# schematic-edited-source.net
KiCad netlist of a schematic drawn in EasyEDA
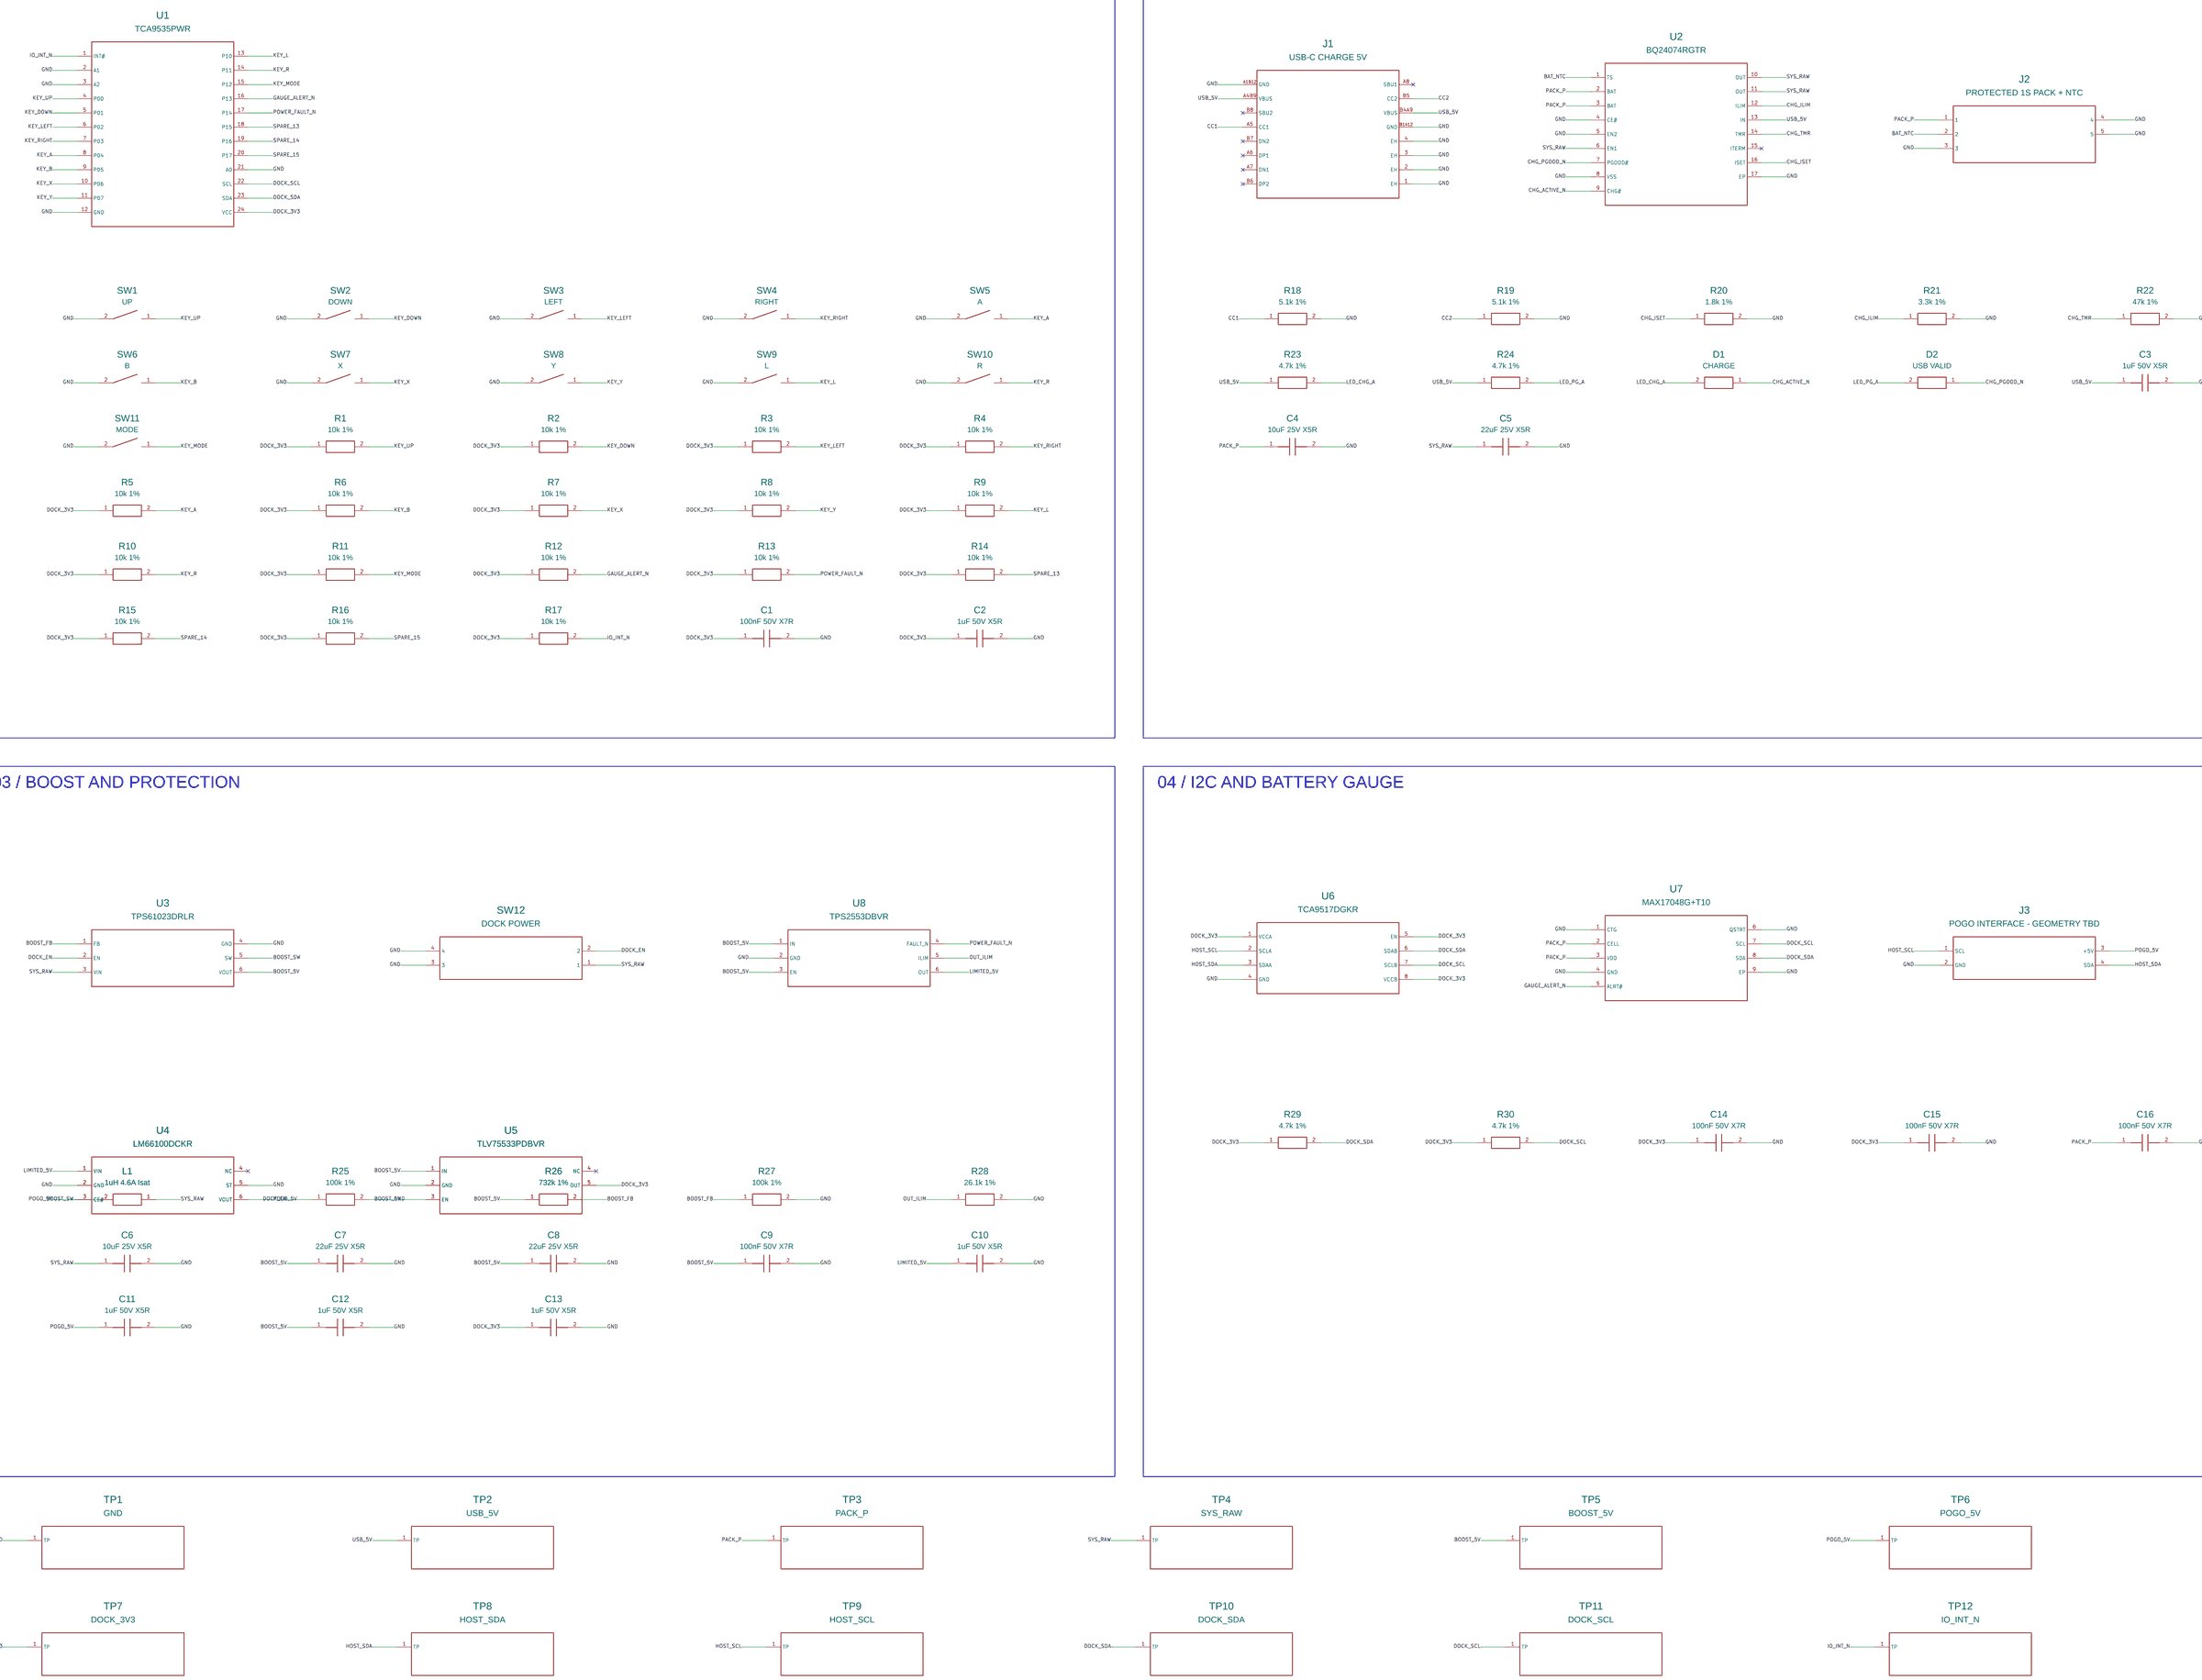
[diagram p0: schematic sheet]

(export (version "E")
  (design (tool "Eeschema 10.0.6"))
  (components
    (comp (ref "C1") (value "100nF 50V X7R") (libsource (lib "") (part "100nF 50V X7R")))
    (comp (ref "C2")
      (value "1uF 50V X5R")
      (fields
        (field (name "Manufacturer Part") "CL10A105KB8NNNC")
        (field (name "Manufacturer") "SAMSUNG(三星)")
      )
      (libsource (lib "") (part "1uF 50V X5R"))
    )
    (comp (ref "C3")
      (value "1uF 50V X5R")
      (fields
        (field (name "Manufacturer Part") "CL10A105KB8NNNC")
        (field (name "Manufacturer") "SAMSUNG(三星)")
      )
      (libsource (lib "") (part "1uF 50V X5R"))
    )
    (comp (ref "C4")
      (value "10uF 25V X5R")
      (fields
        (field (name "Manufacturer Part") "CL10A106MA8NRNC")
        (field (name "Manufacturer") "SAMSUNG(三星)")
      )
      (libsource (lib "") (part "10uF 25V X5R"))
    )
    (comp (ref "C5") (value "22uF 25V X5R") (libsource (lib "") (part "22uF 25V X5R")))
    (comp (ref "C6")
      (value "10uF 25V X5R")
      (fields
        (field (name "Manufacturer Part") "CL10A106MA8NRNC")
        (field (name "Manufacturer") "SAMSUNG(三星)")
      )
      (libsource (lib "") (part "10uF 25V X5R"))
    )
    (comp (ref "C7") (value "22uF 25V X5R") (libsource (lib "") (part "22uF 25V X5R")))
    (comp (ref "C8") (value "22uF 25V X5R") (libsource (lib "") (part "22uF 25V X5R")))
    (comp (ref "C9") (value "100nF 50V X7R") (libsource (lib "") (part "100nF 50V X7R")))
    (comp (ref "C10")
      (value "1uF 50V X5R")
      (fields
        (field (name "Manufacturer Part") "CL10A105KB8NNNC")
        (field (name "Manufacturer") "SAMSUNG(三星)")
      )
      (libsource (lib "") (part "1uF 50V X5R"))
    )
    (comp (ref "C11")
      (value "1uF 50V X5R")
      (fields
        (field (name "Manufacturer Part") "CL10A105KB8NNNC")
        (field (name "Manufacturer") "SAMSUNG(三星)")
      )
      (libsource (lib "") (part "1uF 50V X5R"))
    )
    (comp (ref "C12")
      (value "1uF 50V X5R")
      (fields
        (field (name "Manufacturer Part") "CL10A105KB8NNNC")
        (field (name "Manufacturer") "SAMSUNG(三星)")
      )
      (libsource (lib "") (part "1uF 50V X5R"))
    )
    (comp (ref "C13")
      (value "1uF 50V X5R")
      (fields
        (field (name "Manufacturer Part") "CL10A105KB8NNNC")
        (field (name "Manufacturer") "SAMSUNG(三星)")
      )
      (libsource (lib "") (part "1uF 50V X5R"))
    )
    (comp (ref "C14") (value "100nF 50V X7R") (libsource (lib "") (part "100nF 50V X7R")))
    (comp (ref "C15") (value "100nF 50V X7R") (libsource (lib "") (part "100nF 50V X7R")))
    (comp (ref "C16") (value "100nF 50V X7R") (libsource (lib "") (part "100nF 50V X7R")))
    (comp (ref "D1")
      (value "CHARGE")
      (fields (field (name "Manufacturer Part") "KT-0805黄灯") (field (name "Manufacturer") "KENTO"))
      (libsource (lib "") (part "CHARGE"))
    )
    (comp (ref "D2")
      (value "USB VALID")
      (fields (field (name "Manufacturer Part") "KT-0805黄灯") (field (name "Manufacturer") "KENTO"))
      (libsource (lib "") (part "USB VALID"))
    )
    (comp (ref "J1")
      (value "USB-C CHARGE 5V")
      (fields (field (name "Manufacturer Part") "TYPE-C-31-M-12") (field (name "Manufacturer") "韩国韩荣"))
      (libsource (lib "") (part "USB-C CHARGE 5V"))
    )
    (comp (ref "J2")
      (value "PROTECTED 1S PACK + NTC")
      (fields (field (name "Manufacturer Part") "B3B-PH-SM4-TB(LF)(SN)") (field (name "Manufacturer") "JST"))
      (libsource (lib "") (part "PROTECTED 1S PACK + NTC"))
    )
    (comp (ref "J3")
      (value "POGO INTERFACE - GEOMETRY TBD")
      (libsource (lib "") (part "POGO INTERFACE - GEOMETRY TBD"))
    )
    (comp (ref "L1")
      (value "1uH 4.6A Isat")
      (fields
        (field (name "Manufacturer Part") "FTC201610S1R0MBCA")
        (field (name "Manufacturer") "cjiang(长江微电)")
      )
      (libsource (lib "") (part "1uH 4.6A Isat"))
    )
    (comp (ref "R1")
      (value "10k 1%")
      (fields
        (field (name "Manufacturer Part") "0603WAF1002T5E")
        (field (name "Manufacturer") "UNI-ROYAL(厚声)")
      )
      (libsource (lib "") (part "10k 1%"))
    )
    (comp (ref "R2")
      (value "10k 1%")
      (fields
        (field (name "Manufacturer Part") "0603WAF1002T5E")
        (field (name "Manufacturer") "UNI-ROYAL(厚声)")
      )
      (libsource (lib "") (part "10k 1%"))
    )
    (comp (ref "R3")
      (value "10k 1%")
      (fields
        (field (name "Manufacturer Part") "0603WAF1002T5E")
        (field (name "Manufacturer") "UNI-ROYAL(厚声)")
      )
      (libsource (lib "") (part "10k 1%"))
    )
    (comp (ref "R4")
      (value "10k 1%")
      (fields
        (field (name "Manufacturer Part") "0603WAF1002T5E")
        (field (name "Manufacturer") "UNI-ROYAL(厚声)")
      )
      (libsource (lib "") (part "10k 1%"))
    )
    (comp (ref "R5")
      (value "10k 1%")
      (fields
        (field (name "Manufacturer Part") "0603WAF1002T5E")
        (field (name "Manufacturer") "UNI-ROYAL(厚声)")
      )
      (libsource (lib "") (part "10k 1%"))
    )
    (comp (ref "R6")
      (value "10k 1%")
      (fields
        (field (name "Manufacturer Part") "0603WAF1002T5E")
        (field (name "Manufacturer") "UNI-ROYAL(厚声)")
      )
      (libsource (lib "") (part "10k 1%"))
    )
    (comp (ref "R7")
      (value "10k 1%")
      (fields
        (field (name "Manufacturer Part") "0603WAF1002T5E")
        (field (name "Manufacturer") "UNI-ROYAL(厚声)")
      )
      (libsource (lib "") (part "10k 1%"))
    )
    (comp (ref "R8")
      (value "10k 1%")
      (fields
        (field (name "Manufacturer Part") "0603WAF1002T5E")
        (field (name "Manufacturer") "UNI-ROYAL(厚声)")
      )
      (libsource (lib "") (part "10k 1%"))
    )
    (comp (ref "R9")
      (value "10k 1%")
      (fields
        (field (name "Manufacturer Part") "0603WAF1002T5E")
        (field (name "Manufacturer") "UNI-ROYAL(厚声)")
      )
      (libsource (lib "") (part "10k 1%"))
    )
    (comp (ref "R10")
      (value "10k 1%")
      (fields
        (field (name "Manufacturer Part") "0603WAF1002T5E")
        (field (name "Manufacturer") "UNI-ROYAL(厚声)")
      )
      (libsource (lib "") (part "10k 1%"))
    )
    (comp (ref "R11")
      (value "10k 1%")
      (fields
        (field (name "Manufacturer Part") "0603WAF1002T5E")
        (field (name "Manufacturer") "UNI-ROYAL(厚声)")
      )
      (libsource (lib "") (part "10k 1%"))
    )
    (comp (ref "R12")
      (value "10k 1%")
      (fields
        (field (name "Manufacturer Part") "0603WAF1002T5E")
        (field (name "Manufacturer") "UNI-ROYAL(厚声)")
      )
      (libsource (lib "") (part "10k 1%"))
    )
    (comp (ref "R13")
      (value "10k 1%")
      (fields
        (field (name "Manufacturer Part") "0603WAF1002T5E")
        (field (name "Manufacturer") "UNI-ROYAL(厚声)")
      )
      (libsource (lib "") (part "10k 1%"))
    )
    (comp (ref "R14")
      (value "10k 1%")
      (fields
        (field (name "Manufacturer Part") "0603WAF1002T5E")
        (field (name "Manufacturer") "UNI-ROYAL(厚声)")
      )
      (libsource (lib "") (part "10k 1%"))
    )
    (comp (ref "R15")
      (value "10k 1%")
      (fields
        (field (name "Manufacturer Part") "0603WAF1002T5E")
        (field (name "Manufacturer") "UNI-ROYAL(厚声)")
      )
      (libsource (lib "") (part "10k 1%"))
    )
    (comp (ref "R16")
      (value "10k 1%")
      (fields
        (field (name "Manufacturer Part") "0603WAF1002T5E")
        (field (name "Manufacturer") "UNI-ROYAL(厚声)")
      )
      (libsource (lib "") (part "10k 1%"))
    )
    (comp (ref "R17")
      (value "10k 1%")
      (fields
        (field (name "Manufacturer Part") "0603WAF1002T5E")
        (field (name "Manufacturer") "UNI-ROYAL(厚声)")
      )
      (libsource (lib "") (part "10k 1%"))
    )
    (comp (ref "R18")
      (value "5.1k 1%")
      (fields
        (field (name "Manufacturer Part") "0603WAF5101T5E")
        (field (name "Manufacturer") "UNI-ROYAL(厚声)")
      )
      (libsource (lib "") (part "5.1k 1%"))
    )
    (comp (ref "R19")
      (value "5.1k 1%")
      (fields
        (field (name "Manufacturer Part") "0603WAF5101T5E")
        (field (name "Manufacturer") "UNI-ROYAL(厚声)")
      )
      (libsource (lib "") (part "5.1k 1%"))
    )
    (comp (ref "R20") (value "1.8k 1%") (libsource (lib "") (part "1.8k 1%")))
    (comp (ref "R21") (value "3.3k 1%") (libsource (lib "") (part "3.3k 1%")))
    (comp (ref "R22") (value "47k 1%") (libsource (lib "") (part "47k 1%")))
    (comp (ref "R23")
      (value "4.7k 1%")
      (fields
        (field (name "Manufacturer Part") "0603WAF4701T5E")
        (field (name "Manufacturer") "UNI-ROYAL(厚声)")
      )
      (libsource (lib "") (part "4.7k 1%"))
    )
    (comp (ref "R24")
      (value "4.7k 1%")
      (fields
        (field (name "Manufacturer Part") "0603WAF4701T5E")
        (field (name "Manufacturer") "UNI-ROYAL(厚声)")
      )
      (libsource (lib "") (part "4.7k 1%"))
    )
    (comp (ref "R25")
      (value "100k 1%")
      (fields
        (field (name "Manufacturer Part") "0603WAF1003T5E")
        (field (name "Manufacturer") "UNI-ROYAL(厚声)")
      )
      (libsource (lib "") (part "100k 1%"))
    )
    (comp (ref "R26") (value "732k 1%") (libsource (lib "") (part "732k 1%")))
    (comp (ref "R27")
      (value "100k 1%")
      (fields
        (field (name "Manufacturer Part") "0603WAF1003T5E")
        (field (name "Manufacturer") "UNI-ROYAL(厚声)")
      )
      (libsource (lib "") (part "100k 1%"))
    )
    (comp (ref "R28") (value "26.1k 1%") (libsource (lib "") (part "26.1k 1%")))
    (comp (ref "R29")
      (value "4.7k 1%")
      (fields
        (field (name "Manufacturer Part") "0603WAF4701T5E")
        (field (name "Manufacturer") "UNI-ROYAL(厚声)")
      )
      (libsource (lib "") (part "4.7k 1%"))
    )
    (comp (ref "R30")
      (value "4.7k 1%")
      (fields
        (field (name "Manufacturer Part") "0603WAF4701T5E")
        (field (name "Manufacturer") "UNI-ROYAL(厚声)")
      )
      (libsource (lib "") (part "4.7k 1%"))
    )
    (comp (ref "SW1")
      (value "UP")
      (fields (field (name "Manufacturer Part") "TS-1088-AR02016") (field (name "Manufacturer") "XUNPU(讯普)"))
      (libsource (lib "") (part "UP"))
    )
    (comp (ref "SW2")
      (value "DOWN")
      (fields (field (name "Manufacturer Part") "TS-1088-AR02016") (field (name "Manufacturer") "XUNPU(讯普)"))
      (libsource (lib "") (part "DOWN"))
    )
    (comp (ref "SW3")
      (value "LEFT")
      (fields (field (name "Manufacturer Part") "TS-1088-AR02016") (field (name "Manufacturer") "XUNPU(讯普)"))
      (libsource (lib "") (part "LEFT"))
    )
    (comp (ref "SW4")
      (value "RIGHT")
      (fields (field (name "Manufacturer Part") "TS-1088-AR02016") (field (name "Manufacturer") "XUNPU(讯普)"))
      (libsource (lib "") (part "RIGHT"))
    )
    (comp (ref "SW5")
      (value "A")
      (fields (field (name "Manufacturer Part") "TS-1088-AR02016") (field (name "Manufacturer") "XUNPU(讯普)"))
      (libsource (lib "") (part "A"))
    )
    (comp (ref "SW6")
      (value "B")
      (fields (field (name "Manufacturer Part") "TS-1088-AR02016") (field (name "Manufacturer") "XUNPU(讯普)"))
      (libsource (lib "") (part "B"))
    )
    (comp (ref "SW7")
      (value "X")
      (fields (field (name "Manufacturer Part") "TS-1088-AR02016") (field (name "Manufacturer") "XUNPU(讯普)"))
      (libsource (lib "") (part "X"))
    )
    (comp (ref "SW8")
      (value "Y")
      (fields (field (name "Manufacturer Part") "TS-1088-AR02016") (field (name "Manufacturer") "XUNPU(讯普)"))
      (libsource (lib "") (part "Y"))
    )
    (comp (ref "SW9")
      (value "L")
      (fields (field (name "Manufacturer Part") "TS-1088-AR02016") (field (name "Manufacturer") "XUNPU(讯普)"))
      (libsource (lib "") (part "L"))
    )
    (comp (ref "SW10")
      (value "R")
      (fields (field (name "Manufacturer Part") "TS-1088-AR02016") (field (name "Manufacturer") "XUNPU(讯普)"))
      (libsource (lib "") (part "R"))
    )
    (comp (ref "SW11")
      (value "MODE")
      (fields (field (name "Manufacturer Part") "TS-1088-AR02016") (field (name "Manufacturer") "XUNPU(讯普)"))
      (libsource (lib "") (part "MODE"))
    )
    (comp (ref "SW12")
      (value "DOCK POWER")
      (fields (field (name "Manufacturer Part") "MSK12C02") (field (name "Manufacturer") "SHOU HAN(首韩)"))
      (libsource (lib "") (part "DOCK POWER"))
    )
    (comp (ref "TP1") (value "GND") (libsource (lib "") (part "GND")))
    (comp (ref "TP2") (value "USB_5V") (libsource (lib "") (part "USB_5V")))
    (comp (ref "TP3") (value "PACK_P") (libsource (lib "") (part "PACK_P")))
    (comp (ref "TP4") (value "SYS_RAW") (libsource (lib "") (part "SYS_RAW")))
    (comp (ref "TP5") (value "BOOST_5V") (libsource (lib "") (part "BOOST_5V")))
    (comp (ref "TP6") (value "POGO_5V") (libsource (lib "") (part "POGO_5V")))
    (comp (ref "TP7") (value "DOCK_3V3") (libsource (lib "") (part "DOCK_3V3")))
    (comp (ref "TP8") (value "HOST_SDA") (libsource (lib "") (part "HOST_SDA")))
    (comp (ref "TP9") (value "HOST_SCL") (libsource (lib "") (part "HOST_SCL")))
    (comp (ref "TP10") (value "DOCK_SDA") (libsource (lib "") (part "DOCK_SDA")))
    (comp (ref "TP11") (value "DOCK_SCL") (libsource (lib "") (part "DOCK_SCL")))
    (comp (ref "TP12") (value "IO_INT_N") (libsource (lib "") (part "IO_INT_N")))
    (comp (ref "U1")
      (value "TCA9535PWR")
      (fields (field (name "Manufacturer") "TI(德州仪器)"))
      (libsource (lib "") (part "TCA9535PWR"))
    )
    (comp (ref "U2")
      (value "BQ24074RGTR")
      (fields (field (name "Manufacturer") "TI(德州仪器)"))
      (libsource (lib "") (part "BQ24074RGTR"))
    )
    (comp (ref "U3")
      (value "TPS61023DRLR")
      (fields (field (name "Manufacturer") "TI(德州仪器)"))
      (libsource (lib "") (part "TPS61023DRLR"))
    )
    (comp (ref "U4")
      (value "LM66100DCKR")
      (fields (field (name "Manufacturer") "TI(德州仪器)"))
      (libsource (lib "") (part "LM66100DCKR"))
    )
    (comp (ref "U5")
      (value "TLV75533PDBVR")
      (fields (field (name "Manufacturer") "TI(德州仪器)"))
      (libsource (lib "") (part "TLV75533PDBVR"))
    )
    (comp (ref "U6")
      (value "TCA9517DGKR")
      (fields (field (name "Manufacturer") "TI(德州仪器)"))
      (libsource (lib "") (part "TCA9517DGKR"))
    )
    (comp (ref "U7")
      (value "MAX17048G+T10")
      (fields (field (name "Manufacturer") "ADI(亚德诺)/MAXIM(美信)"))
      (libsource (lib "") (part "MAX17048G+T10"))
    )
    (comp (ref "U8") (value "TPS2553DBVR") (libsource (lib "") (part "TPS2553DBVR")))
  )
  (nets
    (net (code "1") (name "/BAT_NTC") (class "Default")
      (node (ref "J2") (pin "2") (pinfunction "2_2") (pintype "unspecified"))
      (node (ref "U2") (pin "1") (pinfunction "TS_1") (pintype "unspecified"))
    )
    (net (code "2") (name "/BOOST_5V") (class "Default")
      (node (ref "C12") (pin "1") (pintype "unspecified"))
      (node (ref "C7") (pin "1") (pintype "unspecified"))
      (node (ref "C8") (pin "1") (pintype "unspecified"))
      (node (ref "C9") (pin "1") (pintype "unspecified"))
      (node (ref "R26") (pin "1") (pintype "unspecified"))
      (node (ref "TP5") (pin "1") (pinfunction "TP_1") (pintype "unspecified"))
      (node (ref "U3") (pin "6") (pinfunction "VOUT_6") (pintype "unspecified"))
      (node (ref "U5") (pin "1") (pinfunction "IN_1") (pintype "unspecified"))
      (node (ref "U5") (pin "3") (pinfunction "EN_3") (pintype "unspecified"))
      (node (ref "U8") (pin "1") (pinfunction "IN_1") (pintype "unspecified"))
      (node (ref "U8") (pin "3") (pinfunction "EN_3") (pintype "unspecified"))
    )
    (net (code "3") (name "/BOOST_FB") (class "Default")
      (node (ref "R26") (pin "2") (pintype "unspecified"))
      (node (ref "R27") (pin "1") (pintype "unspecified"))
      (node (ref "U3") (pin "1") (pinfunction "FB_1") (pintype "unspecified"))
    )
    (net (code "4") (name "/BOOST_SW") (class "Default")
      (node (ref "C11") (pin "1") (pintype "unspecified"))
      (node (ref "J3") (pin "3") (pinfunction "+5V_3") (pintype "unspecified"))
      (node (ref "L1") (pin "2") (pintype "unspecified"))
      (node (ref "TP6") (pin "1") (pinfunction "TP_1") (pintype "unspecified"))
      (node (ref "U3") (pin "5") (pinfunction "SW_5") (pintype "unspecified"))
      (node (ref "U4") (pin "3") (pinfunction "CE#_3") (pintype "unspecified"))
      (node (ref "U4") (pin "6") (pinfunction "VOUT_6") (pintype "unspecified"))
    )
    (net (code "5") (name "/CC1") (class "Default")
      (node (ref "J1") (pin "A5") (pinfunction "CC1_A5") (pintype "unspecified"))
      (node (ref "R18") (pin "1") (pintype "unspecified"))
    )
    (net (code "6") (name "/CC2") (class "Default")
      (node (ref "J1") (pin "B5") (pinfunction "CC2_B5") (pintype "unspecified"))
      (node (ref "R19") (pin "1") (pintype "unspecified"))
    )
    (net (code "7") (name "/CHG_ACTIVE_N") (class "Default")
      (node (ref "D1") (pin "1") (pintype "unspecified"))
      (node (ref "U2") (pin "9") (pinfunction "CHG#_9") (pintype "unspecified"))
    )
    (net (code "8") (name "/CHG_ILIM") (class "Default")
      (node (ref "R21") (pin "1") (pintype "unspecified"))
      (node (ref "U2") (pin "12") (pinfunction "ILIM_12") (pintype "unspecified"))
    )
    (net (code "9") (name "/CHG_ISET") (class "Default")
      (node (ref "R20") (pin "1") (pintype "unspecified"))
      (node (ref "U2") (pin "16") (pinfunction "ISET_16") (pintype "unspecified"))
    )
    (net (code "10") (name "/CHG_PGOOD_N") (class "Default")
      (node (ref "D2") (pin "1") (pintype "unspecified"))
      (node (ref "U2") (pin "7") (pinfunction "PGOOD#_7") (pintype "unspecified"))
    )
    (net (code "11") (name "/CHG_TMR") (class "Default")
      (node (ref "R22") (pin "1") (pintype "unspecified"))
      (node (ref "U2") (pin "14") (pinfunction "TMR_14") (pintype "unspecified"))
    )
    (net (code "12") (name "/DOCK_3V3") (class "Default")
      (node (ref "C1") (pin "1") (pintype "unspecified"))
      (node (ref "C13") (pin "1") (pintype "unspecified"))
      (node (ref "C14") (pin "1") (pintype "unspecified"))
      (node (ref "C15") (pin "1") (pintype "unspecified"))
      (node (ref "C2") (pin "1") (pintype "unspecified"))
      (node (ref "R1") (pin "1") (pintype "unspecified"))
      (node (ref "R10") (pin "1") (pintype "unspecified"))
      (node (ref "R11") (pin "1") (pintype "unspecified"))
      (node (ref "R12") (pin "1") (pintype "unspecified"))
      (node (ref "R13") (pin "1") (pintype "unspecified"))
      (node (ref "R14") (pin "1") (pintype "unspecified"))
      (node (ref "R15") (pin "1") (pintype "unspecified"))
      (node (ref "R16") (pin "1") (pintype "unspecified"))
      (node (ref "R17") (pin "1") (pintype "unspecified"))
      (node (ref "R2") (pin "1") (pintype "unspecified"))
      (node (ref "R29") (pin "1") (pintype "unspecified"))
      (node (ref "R3") (pin "1") (pintype "unspecified"))
      (node (ref "R30") (pin "1") (pintype "unspecified"))
      (node (ref "R4") (pin "1") (pintype "unspecified"))
      (node (ref "R5") (pin "1") (pintype "unspecified"))
      (node (ref "R6") (pin "1") (pintype "unspecified"))
      (node (ref "R7") (pin "1") (pintype "unspecified"))
      (node (ref "R8") (pin "1") (pintype "unspecified"))
      (node (ref "R9") (pin "1") (pintype "unspecified"))
      (node (ref "TP7") (pin "1") (pinfunction "TP_1") (pintype "unspecified"))
      (node (ref "U1") (pin "24") (pinfunction "VCC_24") (pintype "unspecified"))
      (node (ref "U5") (pin "5") (pinfunction "OUT_5") (pintype "unspecified"))
      (node (ref "U6") (pin "1") (pinfunction "VCCA_1") (pintype "unspecified"))
      (node (ref "U6") (pin "5") (pinfunction "EN_5") (pintype "unspecified"))
      (node (ref "U6") (pin "8") (pinfunction "VCCB_8") (pintype "unspecified"))
    )
    (net (code "13") (name "/DOCK_EN") (class "Default")
      (node (ref "R25") (pin "1") (pintype "unspecified"))
      (node (ref "SW12") (pin "2") (pinfunction "2_2") (pintype "unspecified"))
      (node (ref "U3") (pin "2") (pinfunction "EN_2") (pintype "unspecified"))
    )
    (net (code "14") (name "/DOCK_SCL") (class "Default")
      (node (ref "R30") (pin "2") (pintype "unspecified"))
      (node (ref "TP11") (pin "1") (pinfunction "TP_1") (pintype "unspecified"))
      (node (ref "U1") (pin "22") (pinfunction "SCL_22") (pintype "unspecified"))
      (node (ref "U6") (pin "7") (pinfunction "SCLB_7") (pintype "unspecified"))
      (node (ref "U7") (pin "7") (pinfunction "SCL_7") (pintype "unspecified"))
    )
    (net (code "15") (name "/DOCK_SDA") (class "Default")
      (node (ref "R29") (pin "2") (pintype "unspecified"))
      (node (ref "TP10") (pin "1") (pinfunction "TP_1") (pintype "unspecified"))
      (node (ref "U1") (pin "23") (pinfunction "SDA_23") (pintype "unspecified"))
      (node (ref "U6") (pin "6") (pinfunction "SDAB_6") (pintype "unspecified"))
      (node (ref "U7") (pin "8") (pinfunction "SDA_8") (pintype "unspecified"))
    )
    (net (code "16") (name "/GAUGE_ALERT_N") (class "Default")
      (node (ref "R12") (pin "2") (pintype "unspecified"))
      (node (ref "U1") (pin "16") (pinfunction "P13_16") (pintype "unspecified"))
      (node (ref "U7") (pin "5") (pinfunction "ALRT#_5") (pintype "unspecified"))
    )
    (net (code "17") (name "/GND") (class "Default")
      (node (ref "C1") (pin "2") (pintype "unspecified"))
      (node (ref "C10") (pin "2") (pintype "unspecified"))
      (node (ref "C11") (pin "2") (pintype "unspecified"))
      (node (ref "C12") (pin "2") (pintype "unspecified"))
      (node (ref "C13") (pin "2") (pintype "unspecified"))
      (node (ref "C14") (pin "2") (pintype "unspecified"))
      (node (ref "C15") (pin "2") (pintype "unspecified"))
      (node (ref "C16") (pin "2") (pintype "unspecified"))
      (node (ref "C2") (pin "2") (pintype "unspecified"))
      (node (ref "C3") (pin "2") (pintype "unspecified"))
      (node (ref "C4") (pin "2") (pintype "unspecified"))
      (node (ref "C5") (pin "2") (pintype "unspecified"))
      (node (ref "C6") (pin "2") (pintype "unspecified"))
      (node (ref "C7") (pin "2") (pintype "unspecified"))
      (node (ref "C8") (pin "2") (pintype "unspecified"))
      (node (ref "C9") (pin "2") (pintype "unspecified"))
      (node (ref "J1") (pin "1") (pinfunction "EH_1") (pintype "unspecified"))
      (node (ref "J1") (pin "2") (pinfunction "EH_2") (pintype "unspecified"))
      (node (ref "J1") (pin "3") (pinfunction "EH_3") (pintype "unspecified"))
      (node (ref "J1") (pin "4") (pinfunction "EH_4") (pintype "unspecified"))
      (node (ref "J1") (pin "A1B12") (pinfunction "GND_A1B12") (pintype "unspecified"))
      (node (ref "J1") (pin "B1A12") (pinfunction "GND_B1A12") (pintype "unspecified"))
      (node (ref "J2") (pin "3") (pinfunction "3_3") (pintype "unspecified"))
      (node (ref "J2") (pin "4") (pinfunction "4_4") (pintype "unspecified"))
      (node (ref "J2") (pin "5") (pinfunction "5_5") (pintype "unspecified"))
      (node (ref "J3") (pin "2") (pinfunction "GND_2") (pintype "unspecified"))
      (node (ref "R18") (pin "2") (pintype "unspecified"))
      (node (ref "R19") (pin "2") (pintype "unspecified"))
      (node (ref "R20") (pin "2") (pintype "unspecified"))
      (node (ref "R21") (pin "2") (pintype "unspecified"))
      (node (ref "R22") (pin "2") (pintype "unspecified"))
      (node (ref "R25") (pin "2") (pintype "unspecified"))
      (node (ref "R27") (pin "2") (pintype "unspecified"))
      (node (ref "R28") (pin "2") (pintype "unspecified"))
      (node (ref "SW1") (pin "2") (pintype "unspecified"))
      (node (ref "SW10") (pin "2") (pintype "unspecified"))
      (node (ref "SW11") (pin "2") (pintype "unspecified"))
      (node (ref "SW12") (pin "3") (pinfunction "3_3") (pintype "unspecified"))
      (node (ref "SW12") (pin "4") (pinfunction "4_4") (pintype "unspecified"))
      (node (ref "SW2") (pin "2") (pintype "unspecified"))
      (node (ref "SW3") (pin "2") (pintype "unspecified"))
      (node (ref "SW4") (pin "2") (pintype "unspecified"))
      (node (ref "SW5") (pin "2") (pintype "unspecified"))
      (node (ref "SW6") (pin "2") (pintype "unspecified"))
      (node (ref "SW7") (pin "2") (pintype "unspecified"))
      (node (ref "SW8") (pin "2") (pintype "unspecified"))
      (node (ref "SW9") (pin "2") (pintype "unspecified"))
      (node (ref "TP1") (pin "1") (pinfunction "TP_1") (pintype "unspecified"))
      (node (ref "U1") (pin "12") (pinfunction "GND_12") (pintype "unspecified"))
      (node (ref "U1") (pin "2") (pinfunction "A1_2") (pintype "unspecified"))
      (node (ref "U1") (pin "21") (pinfunction "A0_21") (pintype "unspecified"))
      (node (ref "U1") (pin "3") (pinfunction "A2_3") (pintype "unspecified"))
      (node (ref "U2") (pin "17") (pinfunction "EP_17") (pintype "unspecified"))
      (node (ref "U2") (pin "4") (pinfunction "CE#_4") (pintype "unspecified"))
      (node (ref "U2") (pin "5") (pinfunction "EN2_5") (pintype "unspecified"))
      (node (ref "U2") (pin "8") (pinfunction "VSS_8") (pintype "unspecified"))
      (node (ref "U3") (pin "4") (pinfunction "GND_4") (pintype "unspecified"))
      (node (ref "U4") (pin "2") (pinfunction "GND_2") (pintype "unspecified"))
      (node (ref "U4") (pin "5") (pinfunction "ST_5") (pintype "unspecified"))
      (node (ref "U5") (pin "2") (pinfunction "GND_2") (pintype "unspecified"))
      (node (ref "U6") (pin "4") (pinfunction "GND_4") (pintype "unspecified"))
      (node (ref "U7") (pin "1") (pinfunction "CTG_1") (pintype "unspecified"))
      (node (ref "U7") (pin "4") (pinfunction "GND_4") (pintype "unspecified"))
      (node (ref "U7") (pin "6") (pinfunction "QSTRT_6") (pintype "unspecified"))
      (node (ref "U7") (pin "9") (pinfunction "EP_9") (pintype "unspecified"))
      (node (ref "U8") (pin "2") (pinfunction "GND_2") (pintype "unspecified"))
    )
    (net (code "18") (name "/HOST_SCL") (class "Default")
      (node (ref "J3") (pin "1") (pinfunction "SCL_1") (pintype "unspecified"))
      (node (ref "TP9") (pin "1") (pinfunction "TP_1") (pintype "unspecified"))
      (node (ref "U6") (pin "2") (pinfunction "SCLA_2") (pintype "unspecified"))
    )
    (net (code "19") (name "/HOST_SDA") (class "Default")
      (node (ref "J3") (pin "4") (pinfunction "SDA_4") (pintype "unspecified"))
      (node (ref "TP8") (pin "1") (pinfunction "TP_1") (pintype "unspecified"))
      (node (ref "U6") (pin "3") (pinfunction "SDAA_3") (pintype "unspecified"))
    )
    (net (code "20") (name "/IO_INT_N") (class "Default")
      (node (ref "R17") (pin "2") (pintype "unspecified"))
      (node (ref "TP12") (pin "1") (pinfunction "TP_1") (pintype "unspecified"))
      (node (ref "U1") (pin "1") (pinfunction "INT#_1") (pintype "unspecified"))
    )
    (net (code "21") (name "/KEY_A") (class "Default")
      (node (ref "R5") (pin "2") (pintype "unspecified"))
      (node (ref "SW5") (pin "1") (pintype "unspecified"))
      (node (ref "U1") (pin "8") (pinfunction "P04_8") (pintype "unspecified"))
    )
    (net (code "22") (name "/KEY_B") (class "Default")
      (node (ref "R6") (pin "2") (pintype "unspecified"))
      (node (ref "SW6") (pin "1") (pintype "unspecified"))
      (node (ref "U1") (pin "9") (pinfunction "P05_9") (pintype "unspecified"))
    )
    (net (code "23") (name "/KEY_DOWN") (class "Default")
      (node (ref "R2") (pin "2") (pintype "unspecified"))
      (node (ref "SW2") (pin "1") (pintype "unspecified"))
      (node (ref "U1") (pin "5") (pinfunction "P01_5") (pintype "unspecified"))
    )
    (net (code "24") (name "/KEY_L") (class "Default")
      (node (ref "R9") (pin "2") (pintype "unspecified"))
      (node (ref "SW9") (pin "1") (pintype "unspecified"))
      (node (ref "U1") (pin "13") (pinfunction "P10_13") (pintype "unspecified"))
    )
    (net (code "25") (name "/KEY_LEFT") (class "Default")
      (node (ref "R3") (pin "2") (pintype "unspecified"))
      (node (ref "SW3") (pin "1") (pintype "unspecified"))
      (node (ref "U1") (pin "6") (pinfunction "P02_6") (pintype "unspecified"))
    )
    (net (code "26") (name "/KEY_MODE") (class "Default")
      (node (ref "R11") (pin "2") (pintype "unspecified"))
      (node (ref "SW11") (pin "1") (pintype "unspecified"))
      (node (ref "U1") (pin "15") (pinfunction "P12_15") (pintype "unspecified"))
    )
    (net (code "27") (name "/KEY_R") (class "Default")
      (node (ref "R10") (pin "2") (pintype "unspecified"))
      (node (ref "SW10") (pin "1") (pintype "unspecified"))
      (node (ref "U1") (pin "14") (pinfunction "P11_14") (pintype "unspecified"))
    )
    (net (code "28") (name "/KEY_RIGHT") (class "Default")
      (node (ref "R4") (pin "2") (pintype "unspecified"))
      (node (ref "SW4") (pin "1") (pintype "unspecified"))
      (node (ref "U1") (pin "7") (pinfunction "P03_7") (pintype "unspecified"))
    )
    (net (code "29") (name "/KEY_UP") (class "Default")
      (node (ref "R1") (pin "2") (pintype "unspecified"))
      (node (ref "SW1") (pin "1") (pintype "unspecified"))
      (node (ref "U1") (pin "4") (pinfunction "P00_4") (pintype "unspecified"))
    )
    (net (code "30") (name "/KEY_X") (class "Default")
      (node (ref "R7") (pin "2") (pintype "unspecified"))
      (node (ref "SW7") (pin "1") (pintype "unspecified"))
      (node (ref "U1") (pin "10") (pinfunction "P06_10") (pintype "unspecified"))
    )
    (net (code "31") (name "/KEY_Y") (class "Default")
      (node (ref "R8") (pin "2") (pintype "unspecified"))
      (node (ref "SW8") (pin "1") (pintype "unspecified"))
      (node (ref "U1") (pin "11") (pinfunction "P07_11") (pintype "unspecified"))
    )
    (net (code "32") (name "/LED_CHG_A") (class "Default")
      (node (ref "D1") (pin "2") (pintype "unspecified"))
      (node (ref "R23") (pin "2") (pintype "unspecified"))
    )
    (net (code "33") (name "/LED_PG_A") (class "Default")
      (node (ref "D2") (pin "2") (pintype "unspecified"))
      (node (ref "R24") (pin "2") (pintype "unspecified"))
    )
    (net (code "34") (name "/LIMITED_5V") (class "Default")
      (node (ref "C10") (pin "1") (pintype "unspecified"))
      (node (ref "U4") (pin "1") (pinfunction "VIN_1") (pintype "unspecified"))
      (node (ref "U8") (pin "6") (pinfunction "OUT_6") (pintype "unspecified"))
    )
    (net (code "35") (name "/OUT_ILIM") (class "Default")
      (node (ref "R28") (pin "1") (pintype "unspecified"))
      (node (ref "U8") (pin "5") (pinfunction "ILIM_5") (pintype "unspecified"))
    )
    (net (code "36") (name "/PACK_P") (class "Default")
      (node (ref "C16") (pin "1") (pintype "unspecified"))
      (node (ref "C4") (pin "1") (pintype "unspecified"))
      (node (ref "J2") (pin "1") (pinfunction "1_1") (pintype "unspecified"))
      (node (ref "TP3") (pin "1") (pinfunction "TP_1") (pintype "unspecified"))
      (node (ref "U2") (pin "2") (pinfunction "BAT_2") (pintype "unspecified"))
      (node (ref "U2") (pin "3") (pinfunction "BAT_3") (pintype "unspecified"))
      (node (ref "U7") (pin "2") (pinfunction "CELL_2") (pintype "unspecified"))
      (node (ref "U7") (pin "3") (pinfunction "VDD_3") (pintype "unspecified"))
    )
    (net (code "37") (name "/POWER_FAULT_N") (class "Default")
      (node (ref "R13") (pin "2") (pintype "unspecified"))
      (node (ref "U1") (pin "17") (pinfunction "P14_17") (pintype "unspecified"))
      (node (ref "U8") (pin "4") (pinfunction "FAULT_N_4") (pintype "unspecified"))
    )
    (net (code "38") (name "/SPARE_13") (class "Default")
      (node (ref "R14") (pin "2") (pintype "unspecified"))
      (node (ref "U1") (pin "18") (pinfunction "P15_18") (pintype "unspecified"))
    )
    (net (code "39") (name "/SPARE_14") (class "Default")
      (node (ref "R15") (pin "2") (pintype "unspecified"))
      (node (ref "U1") (pin "19") (pinfunction "P16_19") (pintype "unspecified"))
    )
    (net (code "40") (name "/SPARE_15") (class "Default")
      (node (ref "R16") (pin "2") (pintype "unspecified"))
      (node (ref "U1") (pin "20") (pinfunction "P17_20") (pintype "unspecified"))
    )
    (net (code "41") (name "/SYS_RAW") (class "Default")
      (node (ref "C5") (pin "1") (pintype "unspecified"))
      (node (ref "C6") (pin "1") (pintype "unspecified"))
      (node (ref "L1") (pin "1") (pintype "unspecified"))
      (node (ref "SW12") (pin "1") (pinfunction "1_1") (pintype "unspecified"))
      (node (ref "TP4") (pin "1") (pinfunction "TP_1") (pintype "unspecified"))
      (node (ref "U2") (pin "10") (pinfunction "OUT_10") (pintype "unspecified"))
      (node (ref "U2") (pin "11") (pinfunction "OUT_11") (pintype "unspecified"))
      (node (ref "U2") (pin "6") (pinfunction "EN1_6") (pintype "unspecified"))
      (node (ref "U3") (pin "3") (pinfunction "VIN_3") (pintype "unspecified"))
    )
    (net (code "42") (name "/USB_5V") (class "Default")
      (node (ref "C3") (pin "1") (pintype "unspecified"))
      (node (ref "J1") (pin "A4B9") (pinfunction "VBUS_A4B9") (pintype "unspecified"))
      (node (ref "J1") (pin "B4A9") (pinfunction "VBUS_B4A9") (pintype "unspecified"))
      (node (ref "R23") (pin "1") (pintype "unspecified"))
      (node (ref "R24") (pin "1") (pintype "unspecified"))
      (node (ref "TP2") (pin "1") (pinfunction "TP_1") (pintype "unspecified"))
      (node (ref "U2") (pin "13") (pinfunction "IN_13") (pintype "unspecified"))
    )
    (net (code "43") (name "unconnected-(J1-DN1-PadA7)") (class "Default")
      (node (ref "J1") (pin "A7") (pinfunction "DN1_A7") (pintype "unspecified+no_connect"))
    )
    (net (code "44") (name "unconnected-(J1-DN2-PadB7)") (class "Default")
      (node (ref "J1") (pin "B7") (pinfunction "DN2_B7") (pintype "unspecified+no_connect"))
    )
    (net (code "45") (name "unconnected-(J1-DP1-PadA6)") (class "Default")
      (node (ref "J1") (pin "A6") (pinfunction "DP1_A6") (pintype "unspecified+no_connect"))
    )
    (net (code "46") (name "unconnected-(J1-DP2-PadB6)") (class "Default")
      (node (ref "J1") (pin "B6") (pinfunction "DP2_B6") (pintype "unspecified+no_connect"))
    )
    (net (code "47") (name "unconnected-(J1-SBU1-PadA8)") (class "Default")
      (node (ref "J1") (pin "A8") (pinfunction "SBU1_A8") (pintype "unspecified+no_connect"))
    )
    (net (code "48") (name "unconnected-(J1-SBU2-PadB8)") (class "Default")
      (node (ref "J1") (pin "B8") (pinfunction "SBU2_B8") (pintype "unspecified+no_connect"))
    )
    (net (code "49") (name "unconnected-(U2-ITERM-Pad15)") (class "Default")
      (node (ref "U2") (pin "15") (pinfunction "ITERM_15") (pintype "unspecified+no_connect"))
    )
    (net (code "50") (name "unconnected-(U4-NC-Pad4)") (class "Default")
      (node (ref "U4") (pin "4") (pinfunction "NC_4") (pintype "unspecified+no_connect"))
    )
    (net (code "51") (name "unconnected-(U5-NC-Pad4)") (class "Default")
      (node (ref "U5") (pin "4") (pinfunction "NC_4") (pintype "unspecified+no_connect"))
    )
  )
)
